# experimental_substrate.net
KiCad netlist of a schematic drawn in EAGLE
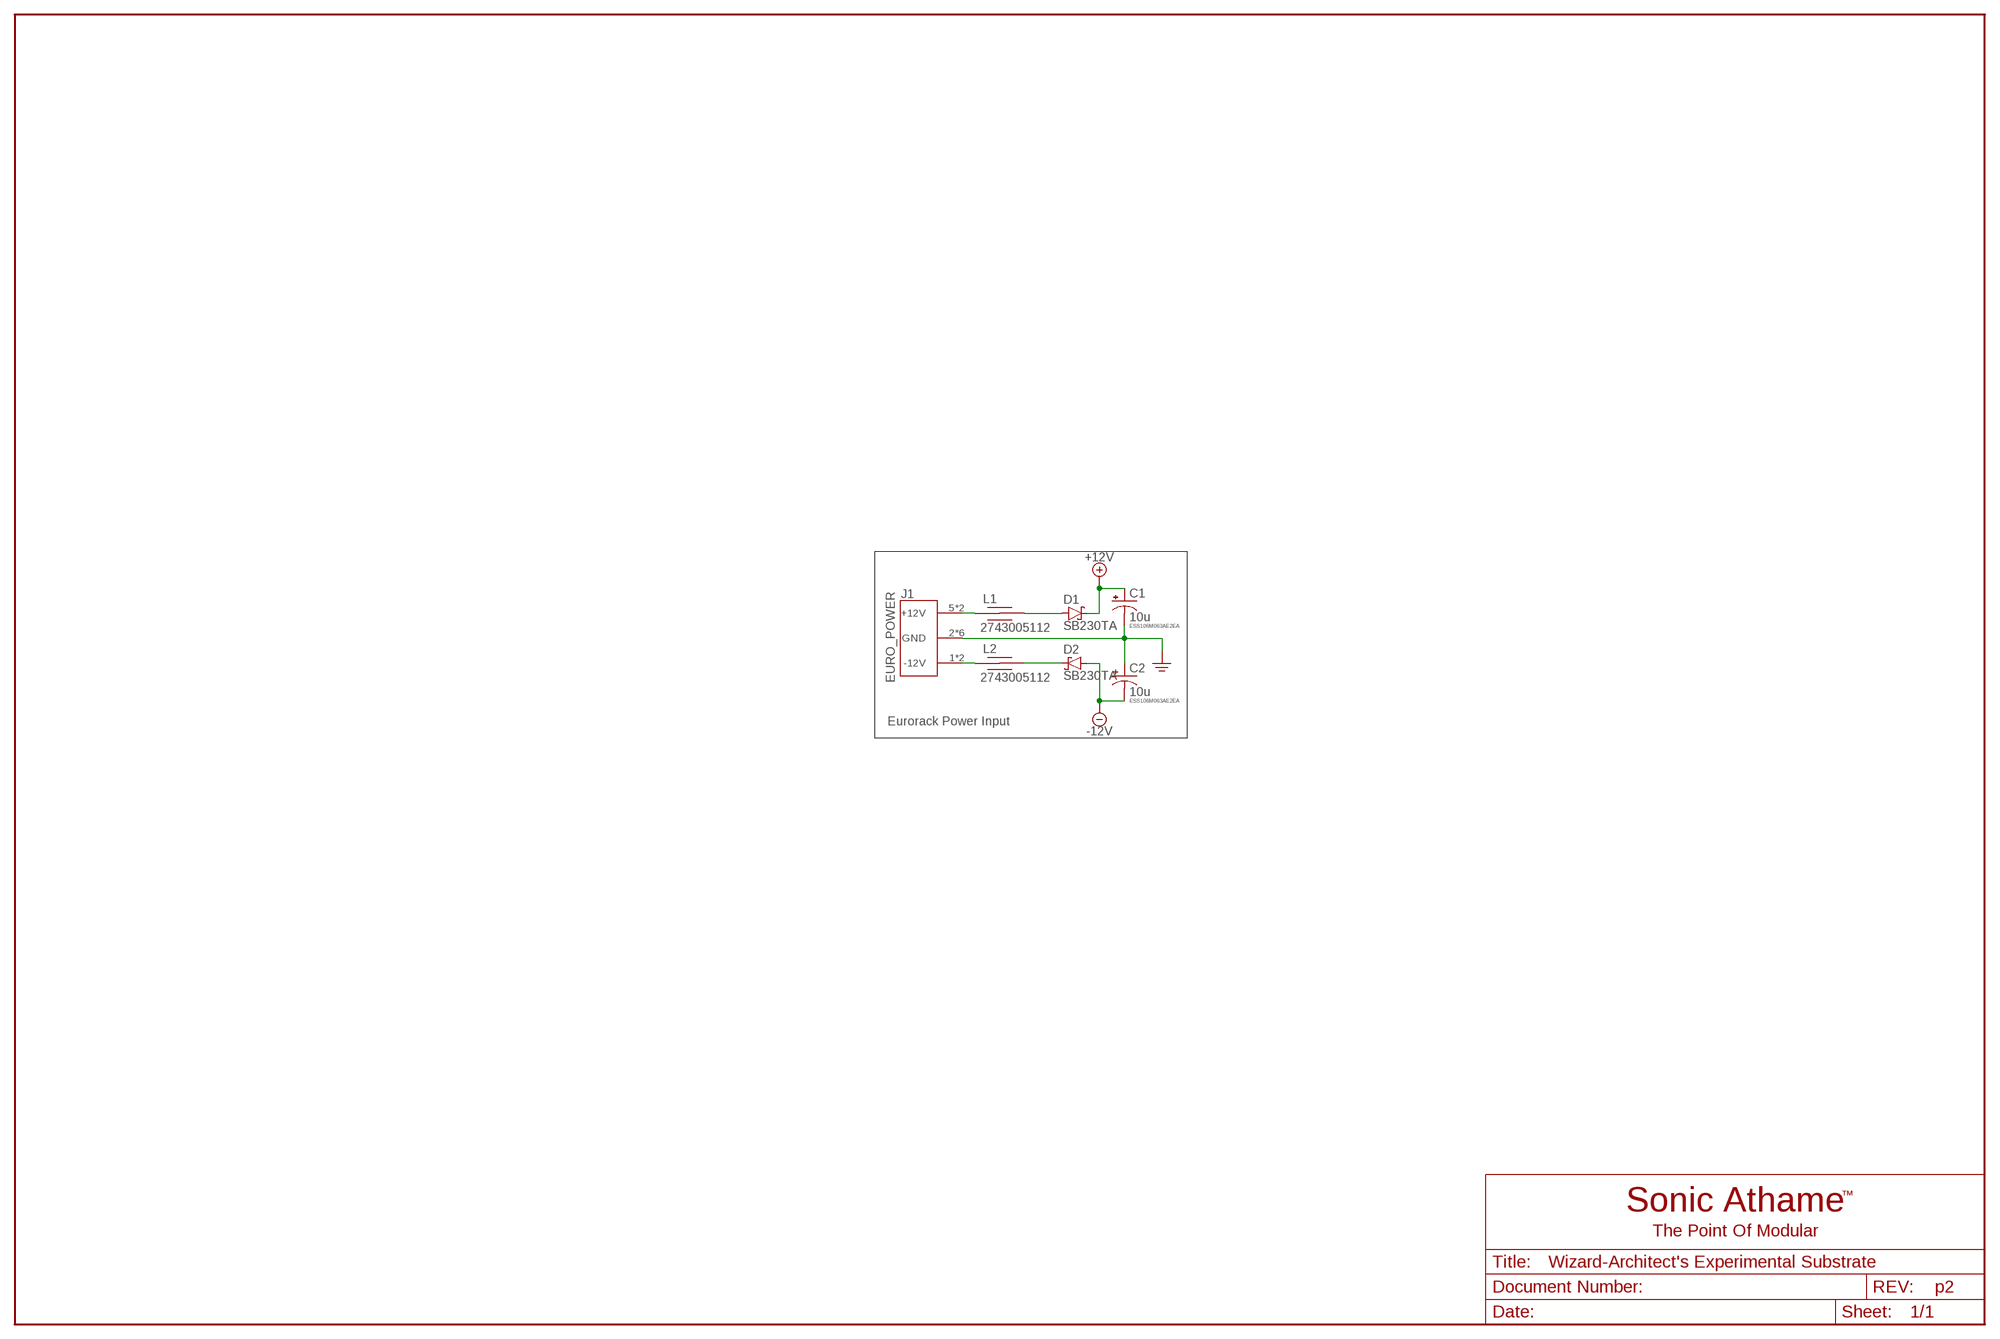
[diagram p0: schematic, sheet 1]

(export (version "E")
  (design (tool "Eeschema 10.0.6"))
  (components
    (comp (ref "C1")
      (value "10u")
      (footprint "eagle-import:TT2D5")
      (libsource (lib "eagle-import") (part "CAP_POLLYTIC_V"))
    )
    (comp (ref "C2")
      (value "10u")
      (footprint "eagle-import:TT2D5")
      (libsource (lib "eagle-import") (part "CAP_POLLYTIC_V"))
    )
    (comp (ref "D1")
      (value "SB230TA")
      (footprint "eagle-import:0207_2V-POL")
      (libsource (lib "eagle-import") (part "SCHOTTKY_THT"))
    )
    (comp (ref "D2")
      (value "SB230TA")
      (footprint "eagle-import:0207_2V-POL")
      (libsource (lib "eagle-import") (part "SCHOTTKY_THT"))
    )
    (comp (ref "J1")
      (value "EURO_POWER")
      (footprint "eagle-import:EURO_POWER")
      (libsource (lib "eagle-import") (part "EURO_POWER"))
    )
    (comp (ref "L1")
      (value "2743005112")
      (footprint "eagle-import:0207_2V")
      (libsource (lib "eagle-import") (part "FERRITE_THT"))
    )
    (comp (ref "L2")
      (value "2743005112")
      (footprint "eagle-import:0207_2V")
      (libsource (lib "eagle-import") (part "FERRITE_THT"))
    )
  )
  (nets
    (net (code "1") (name "+12V") (class "Default")
      (node (ref "C1") (pin "+") (pinfunction "+_+") (pintype "passive"))
      (node (ref "D1") (pin "C") (pinfunction "C_C") (pintype "passive"))
    )
    (net (code "2") (name "-12V") (class "Default")
      (node (ref "C2") (pin "-") (pinfunction "-_-") (pintype "passive"))
      (node (ref "D2") (pin "A") (pinfunction "A_A") (pintype "passive"))
    )
    (net (code "3") (name "GND") (class "Default")
      (node (ref "C1") (pin "-") (pinfunction "-_-") (pintype "passive"))
      (node (ref "C2") (pin "+") (pinfunction "+_+") (pintype "passive"))
      (node (ref "J1") (pin "2") (pinfunction "GND_2") (pintype "bidirectional"))
      (node (ref "J1") (pin "3") (pinfunction "GND_3") (pintype "bidirectional"))
      (node (ref "J1") (pin "4") (pinfunction "GND_4") (pintype "bidirectional"))
      (node (ref "J1") (pin "7") (pinfunction "GND_7") (pintype "bidirectional"))
      (node (ref "J1") (pin "8") (pinfunction "GND_8") (pintype "bidirectional"))
      (node (ref "J1") (pin "9") (pinfunction "GND_9") (pintype "bidirectional"))
    )
    (net (code "4") (name "Net-(L1-P$1)") (class "Default")
      (node (ref "J1") (pin "5") (pinfunction "+12V_5") (pintype "bidirectional"))
      (node (ref "J1") (pin "6") (pinfunction "+12V_6") (pintype "bidirectional"))
      (node (ref "L1") (pin "1") (pinfunction "P$1_1") (pintype "bidirectional"))
    )
    (net (code "5") (name "Net-(L1-P$2)") (class "Default")
      (node (ref "D1") (pin "A") (pinfunction "A_A") (pintype "passive"))
      (node (ref "L1") (pin "2") (pinfunction "P$2_2") (pintype "bidirectional"))
    )
    (net (code "6") (name "Net-(L2-P$1)") (class "Default")
      (node (ref "J1") (pin "1") (pinfunction "-12V_1") (pintype "bidirectional"))
      (node (ref "J1") (pin "10") (pinfunction "-12V_10") (pintype "bidirectional"))
      (node (ref "L2") (pin "1") (pinfunction "P$1_1") (pintype "bidirectional"))
    )
    (net (code "7") (name "Net-(L2-P$2)") (class "Default")
      (node (ref "D2") (pin "C") (pinfunction "C_C") (pintype "passive"))
      (node (ref "L2") (pin "2") (pinfunction "P$2_2") (pintype "bidirectional"))
    )
  )
)
